# royer_1kw.net
KiCad netlist of a schematic drawn in EAGLE
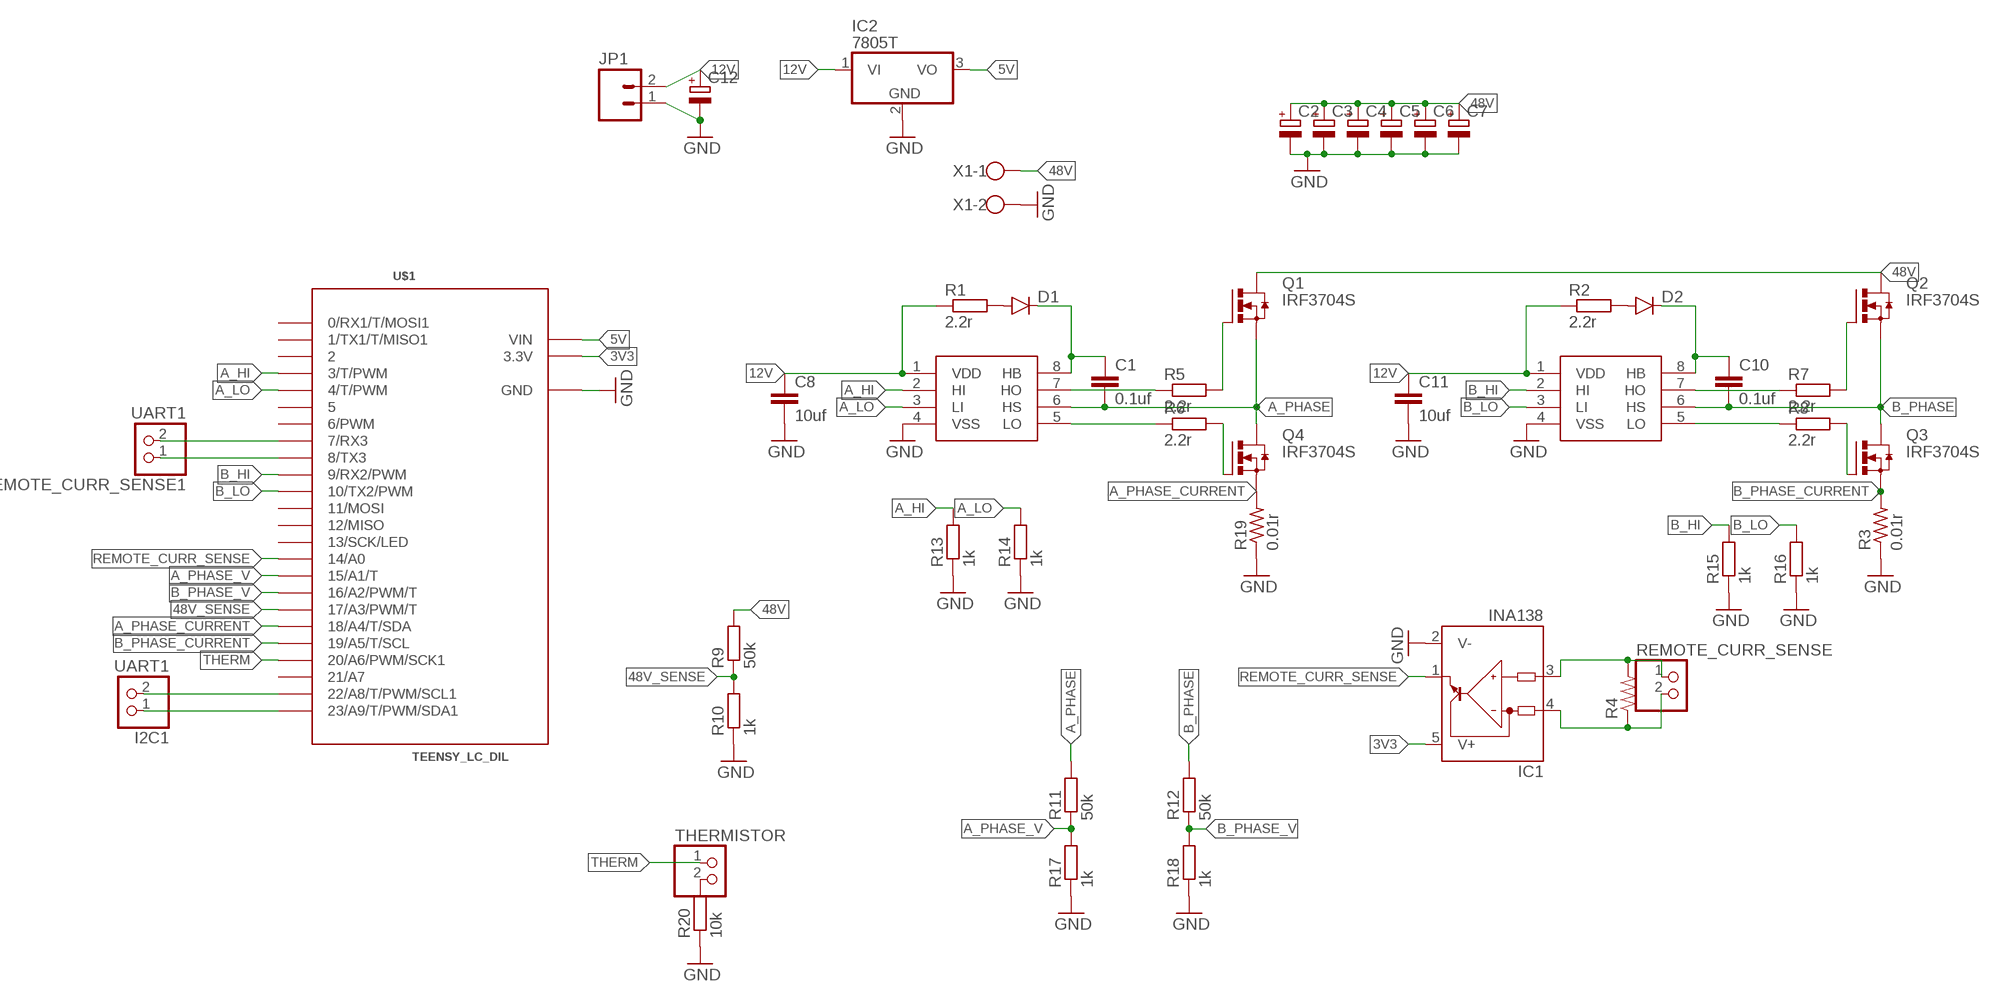
[diagram p0: schematic, sheet 1]

(export (version "E")
  (design (tool "Eeschema 10.0.6"))
  (components
    (comp (ref "C1")
      (value "0.1uf")
      (footprint "eagle-import:C0603")
      (libsource (lib "eagle-import") (part "C-EUC0603"))
    )
    (comp (ref "C2")
      (value "CPOL-EUE7.5-16")
      (footprint "eagle-import:E7,5-16")
      (libsource (lib "eagle-import") (part "CPOL-EUE7.5-16"))
    )
    (comp (ref "C3")
      (value "CPOL-EUE7.5-16")
      (footprint "eagle-import:E7,5-16")
      (libsource (lib "eagle-import") (part "CPOL-EUE7.5-16"))
    )
    (comp (ref "C4")
      (value "CPOL-EUE7.5-16")
      (footprint "eagle-import:E7,5-16")
      (libsource (lib "eagle-import") (part "CPOL-EUE7.5-16"))
    )
    (comp (ref "C5")
      (value "CPOL-EUE7.5-16")
      (footprint "eagle-import:E7,5-16")
      (libsource (lib "eagle-import") (part "CPOL-EUE7.5-16"))
    )
    (comp (ref "C6")
      (value "CPOL-EUE7.5-16")
      (footprint "eagle-import:E7,5-16")
      (libsource (lib "eagle-import") (part "CPOL-EUE7.5-16"))
    )
    (comp (ref "C7")
      (value "CPOL-EUE7.5-16")
      (footprint "eagle-import:E7,5-16")
      (libsource (lib "eagle-import") (part "CPOL-EUE7.5-16"))
    )
    (comp (ref "C8")
      (value "10uf")
      (footprint "eagle-import:C0805")
      (libsource (lib "eagle-import") (part "C-EUC0805"))
    )
    (comp (ref "C10")
      (value "0.1uf")
      (footprint "eagle-import:C0603")
      (libsource (lib "eagle-import") (part "C-EUC0603"))
    )
    (comp (ref "C11")
      (value "10uf")
      (footprint "eagle-import:C0805")
      (libsource (lib "eagle-import") (part "C-EUC0805"))
    )
    (comp (ref "C12")
      (value "CPOL-EUE2.5-7")
      (footprint "eagle-import:E2,5-7")
      (libsource (lib "eagle-import") (part "CPOL-EUE2.5-7"))
    )
    (comp (ref "D1")
      (value "DIODESMA")
      (footprint "eagle-import:SMA-DIODE")
      (libsource (lib "eagle-import") (part "DIODESMA"))
    )
    (comp (ref "D2")
      (value "DIODESMA")
      (footprint "eagle-import:SMA-DIODE")
      (libsource (lib "eagle-import") (part "DIODESMA"))
    )
    (comp (ref "I2C1")
      (value "UART1")
      (footprint "eagle-import:1X02")
      (libsource (lib "eagle-import") (part "PINHD-1X2"))
    )
    (comp (ref "IC1")
      (value "INA138")
      (footprint "eagle-import:SOT23-5")
      (fields (field (name "MF") "TEXAS INSTRUMENTS") (field (name "MPN") "INA138NA/250"))
      (libsource (lib "eagle-import") (part "INA138"))
    )
    (comp (ref "IC2")
      (value "7805T")
      (footprint "eagle-import:TO220H")
      (libsource (lib "eagle-import") (part "78T05"))
    )
    (comp (ref "JP1")
      (value "M023.5MM")
      (footprint "eagle-import:SCREWTERMINAL-3.5MM-2")
      (libsource (lib "eagle-import") (part "M023.5MM"))
    )
    (comp (ref "Q1")
      (value "IRF3704S")
      (footprint "eagle-import:D2PACK")
      (libsource (lib "eagle-import") (part "IRF3704S"))
    )
    (comp (ref "Q2")
      (value "IRF3704S")
      (footprint "eagle-import:D2PACK")
      (libsource (lib "eagle-import") (part "IRF3704S"))
    )
    (comp (ref "Q3")
      (value "IRF3704S")
      (footprint "eagle-import:D2PACK")
      (libsource (lib "eagle-import") (part "IRF3704S"))
    )
    (comp (ref "Q4")
      (value "IRF3704S")
      (footprint "eagle-import:D2PACK")
      (libsource (lib "eagle-import") (part "IRF3704S"))
    )
    (comp (ref "R1")
      (value "2.2r")
      (footprint "eagle-import:R1210")
      (libsource (lib "eagle-import") (part "R-EU_R1210"))
    )
    (comp (ref "R2")
      (value "2.2r")
      (footprint "eagle-import:R1210")
      (libsource (lib "eagle-import") (part "R-EU_R1210"))
    )
    (comp (ref "R3")
      (value "0.01r")
      (footprint "eagle-import:R3225")
      (libsource (lib "eagle-import") (part "R-US_R3225"))
    )
    (comp (ref "R4")
      (value "RESISTOR1206")
      (footprint "eagle-import:1206")
      (libsource (lib "eagle-import") (part "RESISTOR1206"))
    )
    (comp (ref "R5")
      (value "2.2r")
      (footprint "eagle-import:R1210")
      (libsource (lib "eagle-import") (part "R-EU_R1210"))
    )
    (comp (ref "R6")
      (value "2.2r")
      (footprint "eagle-import:R1210")
      (libsource (lib "eagle-import") (part "R-EU_R1210"))
    )
    (comp (ref "R7")
      (value "2.2r")
      (footprint "eagle-import:R1210")
      (libsource (lib "eagle-import") (part "R-EU_R1210"))
    )
    (comp (ref "R8")
      (value "2.2r")
      (footprint "eagle-import:R1210")
      (libsource (lib "eagle-import") (part "R-EU_R1210"))
    )
    (comp (ref "R9")
      (value "50k")
      (footprint "eagle-import:R0603")
      (libsource (lib "eagle-import") (part "R-EU_R0603"))
    )
    (comp (ref "R10")
      (value "1k")
      (footprint "eagle-import:R0603")
      (libsource (lib "eagle-import") (part "R-EU_R0603"))
    )
    (comp (ref "R11")
      (value "50k")
      (footprint "eagle-import:R0603")
      (libsource (lib "eagle-import") (part "R-EU_R0603"))
    )
    (comp (ref "R12")
      (value "50k")
      (footprint "eagle-import:R0603")
      (libsource (lib "eagle-import") (part "R-EU_R0603"))
    )
    (comp (ref "R13")
      (value "1k")
      (footprint "eagle-import:R0603")
      (libsource (lib "eagle-import") (part "R-EU_R0603"))
    )
    (comp (ref "R14")
      (value "1k")
      (footprint "eagle-import:R0603")
      (libsource (lib "eagle-import") (part "R-EU_R0603"))
    )
    (comp (ref "R15")
      (value "1k")
      (footprint "eagle-import:R0603")
      (libsource (lib "eagle-import") (part "R-EU_R0603"))
    )
    (comp (ref "R16")
      (value "1k")
      (footprint "eagle-import:R0603")
      (libsource (lib "eagle-import") (part "R-EU_R0603"))
    )
    (comp (ref "R17")
      (value "1k")
      (footprint "eagle-import:R0603")
      (libsource (lib "eagle-import") (part "R-EU_R0603"))
    )
    (comp (ref "R18")
      (value "1k")
      (footprint "eagle-import:R0603")
      (libsource (lib "eagle-import") (part "R-EU_R0603"))
    )
    (comp (ref "R19")
      (value "0.01r")
      (footprint "eagle-import:R3225")
      (libsource (lib "eagle-import") (part "R-US_R3225"))
    )
    (comp (ref "R20")
      (value "10k")
      (footprint "eagle-import:R0603")
      (libsource (lib "eagle-import") (part "R-EU_R0603"))
    )
    (comp (ref "REMOTE_CURR_SENSE")
      (value "PINHD-1X2")
      (footprint "eagle-import:1X02")
      (libsource (lib "eagle-import") (part "PINHD-1X2"))
    )
    (comp (ref "REMOTE_CURR_SENSE1")
      (value "UART1")
      (footprint "eagle-import:1X02")
      (libsource (lib "eagle-import") (part "PINHD-1X2"))
    )
    (comp (ref "THERMISTOR")
      (value "PINHD-1X2")
      (footprint "eagle-import:1X02")
      (libsource (lib "eagle-import") (part "PINHD-1X2"))
    )
    (comp (ref "U$1")
      (value "TEENSY_LC_DIL")
      (footprint "eagle-import:TEENSY_3.0-3.2&LC_DIL")
      (libsource (lib "eagle-import") (part "TEENSY_LC_DIL"))
    )
    (comp (ref "U$2")
      (value "LM5109")
      (footprint "eagle-import:SOIC8")
      (libsource (lib "eagle-import") (part "LM5109"))
    )
    (comp (ref "U$4")
      (value "LM5109")
      (footprint "eagle-import:SOIC8")
      (libsource (lib "eagle-import") (part "LM5109"))
    )
    (comp (ref "X1")
      (value "W237-102")
      (footprint "eagle-import:W237-102")
      (fields (field (name "MPN") "237-102"))
      (libsource (lib "eagle-import") (part "W237-102"))
    )
  )
  (nets
    (net (code "1") (name "3V3") (class "Default")
      (node (ref "IC1") (pin "5") (pinfunction "V+_5") (pintype "power_in"))
      (node (ref "U$1") (pin "3.3V") (pinfunction "3.3V_3.3V") (pintype "power_in"))
    )
    (net (code "2") (name "5V") (class "Default")
      (node (ref "IC2") (pin "3") (pinfunction "VO_3") (pintype "passive"))
      (node (ref "U$1") (pin "VIN") (pinfunction "VIN_VIN") (pintype "power_in"))
    )
    (net (code "3") (name "12V") (class "Default")
      (node (ref "C11") (pin "1") (pinfunction "1_1") (pintype "passive"))
      (node (ref "C12") (pin "+") (pinfunction "+_+") (pintype "passive"))
      (node (ref "C8") (pin "1") (pinfunction "1_1") (pintype "passive"))
      (node (ref "IC2") (pin "1") (pinfunction "VI_1") (pintype "input"))
      (node (ref "JP1") (pin "2") (pinfunction "2_2") (pintype "passive"))
      (node (ref "R1") (pin "1") (pinfunction "1_1") (pintype "passive"))
      (node (ref "R2") (pin "1") (pinfunction "1_1") (pintype "passive"))
      (node (ref "U$2") (pin "1") (pinfunction "VDD_1") (pintype "bidirectional"))
      (node (ref "U$4") (pin "1") (pinfunction "VDD_1") (pintype "bidirectional"))
    )
    (net (code "4") (name "48V") (class "Default")
      (node (ref "C2") (pin "+") (pinfunction "+_+") (pintype "passive"))
      (node (ref "C3") (pin "+") (pinfunction "+_+") (pintype "passive"))
      (node (ref "C4") (pin "+") (pinfunction "+_+") (pintype "passive"))
      (node (ref "C5") (pin "+") (pinfunction "+_+") (pintype "passive"))
      (node (ref "C6") (pin "+") (pinfunction "+_+") (pintype "passive"))
      (node (ref "C7") (pin "+") (pinfunction "+_+") (pintype "passive"))
      (node (ref "Q1") (pin "2") (pinfunction "D_2") (pintype "passive"))
      (node (ref "Q2") (pin "2") (pinfunction "D_2") (pintype "passive"))
      (node (ref "R9") (pin "2") (pinfunction "2_2") (pintype "passive"))
      (node (ref "X1") (pin "1") (pinfunction "KL_1") (pintype "passive"))
    )
    (net (code "5") (name "48V_SENSE") (class "Default")
      (node (ref "R10") (pin "2") (pinfunction "2_2") (pintype "passive"))
      (node (ref "R9") (pin "1") (pinfunction "1_1") (pintype "passive"))
      (node (ref "U$1") (pin "17/A3") (pinfunction "17/A3/PWM/T_17/A3") (pintype "bidirectional"))
    )
    (net (code "6") (name "A_HI") (class "Default")
      (node (ref "R13") (pin "2") (pinfunction "2_2") (pintype "passive"))
      (node (ref "U$1") (pin "3") (pinfunction "3/T/PWM_3") (pintype "bidirectional"))
      (node (ref "U$2") (pin "2") (pinfunction "HI_2") (pintype "bidirectional"))
    )
    (net (code "7") (name "A_LO") (class "Default")
      (node (ref "R14") (pin "2") (pinfunction "2_2") (pintype "passive"))
      (node (ref "U$1") (pin "4") (pinfunction "4/T/PWM_4") (pintype "bidirectional"))
      (node (ref "U$2") (pin "3") (pinfunction "LI_3") (pintype "bidirectional"))
    )
    (net (code "8") (name "A_PHASE") (class "Default")
      (node (ref "C1") (pin "2") (pinfunction "2_2") (pintype "passive"))
      (node (ref "Q1") (pin "3") (pinfunction "S_3") (pintype "passive"))
      (node (ref "Q4") (pin "2") (pinfunction "D_2") (pintype "passive"))
      (node (ref "R11") (pin "2") (pinfunction "2_2") (pintype "passive"))
      (node (ref "U$2") (pin "6") (pinfunction "HS_6") (pintype "bidirectional"))
    )
    (net (code "9") (name "A_PHASE_CURRENT") (class "Default")
      (node (ref "Q4") (pin "3") (pinfunction "S_3") (pintype "passive"))
      (node (ref "R19") (pin "2") (pinfunction "2_2") (pintype "passive"))
      (node (ref "U$1") (pin "18/A4") (pinfunction "18/A4/T/SDA_18/A4") (pintype "bidirectional"))
    )
    (net (code "10") (name "A_PHASE_V") (class "Default")
      (node (ref "R11") (pin "1") (pinfunction "1_1") (pintype "passive"))
      (node (ref "R17") (pin "2") (pinfunction "2_2") (pintype "passive"))
      (node (ref "U$1") (pin "15/A1") (pinfunction "15/A1/T_15/A1") (pintype "bidirectional"))
    )
    (net (code "11") (name "B_HI") (class "Default")
      (node (ref "R15") (pin "2") (pinfunction "2_2") (pintype "passive"))
      (node (ref "U$1") (pin "9") (pinfunction "9/RX2/PWM_9") (pintype "bidirectional"))
      (node (ref "U$4") (pin "2") (pinfunction "HI_2") (pintype "bidirectional"))
    )
    (net (code "12") (name "B_LO") (class "Default")
      (node (ref "R16") (pin "2") (pinfunction "2_2") (pintype "passive"))
      (node (ref "U$1") (pin "10") (pinfunction "10/TX2/PWM_10") (pintype "bidirectional"))
      (node (ref "U$4") (pin "3") (pinfunction "LI_3") (pintype "bidirectional"))
    )
    (net (code "13") (name "B_PHASE") (class "Default")
      (node (ref "C10") (pin "2") (pinfunction "2_2") (pintype "passive"))
      (node (ref "Q2") (pin "3") (pinfunction "S_3") (pintype "passive"))
      (node (ref "Q3") (pin "2") (pinfunction "D_2") (pintype "passive"))
      (node (ref "R12") (pin "2") (pinfunction "2_2") (pintype "passive"))
      (node (ref "U$4") (pin "6") (pinfunction "HS_6") (pintype "bidirectional"))
    )
    (net (code "14") (name "B_PHASE_CURRENT") (class "Default")
      (node (ref "Q3") (pin "3") (pinfunction "S_3") (pintype "passive"))
      (node (ref "R3") (pin "2") (pinfunction "2_2") (pintype "passive"))
      (node (ref "U$1") (pin "19/A5") (pinfunction "19/A5/T/SCL_19/A5") (pintype "bidirectional"))
    )
    (net (code "15") (name "B_PHASE_V") (class "Default")
      (node (ref "R12") (pin "1") (pinfunction "1_1") (pintype "passive"))
      (node (ref "R18") (pin "2") (pinfunction "2_2") (pintype "passive"))
      (node (ref "U$1") (pin "16/A2") (pinfunction "16/A2/PWM/T_16/A2") (pintype "bidirectional"))
    )
    (net (code "16") (name "GND") (class "Default")
      (node (ref "C11") (pin "2") (pinfunction "2_2") (pintype "passive"))
      (node (ref "C12") (pin "-") (pinfunction "-_-") (pintype "passive"))
      (node (ref "C2") (pin "-") (pinfunction "-_-") (pintype "passive"))
      (node (ref "C3") (pin "-") (pinfunction "-_-") (pintype "passive"))
      (node (ref "C4") (pin "-") (pinfunction "-_-") (pintype "passive"))
      (node (ref "C5") (pin "-") (pinfunction "-_-") (pintype "passive"))
      (node (ref "C6") (pin "-") (pinfunction "-_-") (pintype "passive"))
      (node (ref "C7") (pin "-") (pinfunction "-_-") (pintype "passive"))
      (node (ref "C8") (pin "2") (pinfunction "2_2") (pintype "passive"))
      (node (ref "IC1") (pin "2") (pinfunction "V-_2") (pintype "power_in"))
      (node (ref "IC2") (pin "2") (pinfunction "GND_2") (pintype "passive"))
      (node (ref "JP1") (pin "1") (pinfunction "1_1") (pintype "passive"))
      (node (ref "R10") (pin "1") (pinfunction "1_1") (pintype "passive"))
      (node (ref "R13") (pin "1") (pinfunction "1_1") (pintype "passive"))
      (node (ref "R14") (pin "1") (pinfunction "1_1") (pintype "passive"))
      (node (ref "R15") (pin "1") (pinfunction "1_1") (pintype "passive"))
      (node (ref "R16") (pin "1") (pinfunction "1_1") (pintype "passive"))
      (node (ref "R17") (pin "1") (pinfunction "1_1") (pintype "passive"))
      (node (ref "R18") (pin "1") (pinfunction "1_1") (pintype "passive"))
      (node (ref "R19") (pin "1") (pinfunction "1_1") (pintype "passive"))
      (node (ref "R20") (pin "1") (pinfunction "1_1") (pintype "passive"))
      (node (ref "R3") (pin "1") (pinfunction "1_1") (pintype "passive"))
      (node (ref "U$1") (pin "AGND") (pinfunction "GND_AGND") (pintype "power_in"))
      (node (ref "U$1") (pin "GND") (pinfunction "GND_GND") (pintype "power_in"))
      (node (ref "U$2") (pin "4") (pinfunction "VSS_4") (pintype "bidirectional"))
      (node (ref "U$4") (pin "4") (pinfunction "VSS_4") (pintype "bidirectional"))
      (node (ref "X1") (pin "2") (pinfunction "KL_2") (pintype "passive"))
    )
    (net (code "17") (name "Net-(D1-PadA)") (class "Default")
      (node (ref "D1") (pin "A") (pinfunction "A_A") (pintype "passive"))
      (node (ref "R1") (pin "2") (pinfunction "2_2") (pintype "passive"))
    )
    (net (code "18") (name "Net-(D2-PadA)") (class "Default")
      (node (ref "D2") (pin "A") (pinfunction "A_A") (pintype "passive"))
      (node (ref "R2") (pin "2") (pinfunction "2_2") (pintype "passive"))
    )
    (net (code "19") (name "Net-(IC1-IN+)") (class "Default")
      (node (ref "IC1") (pin "3") (pinfunction "IN+_3") (pintype "input"))
      (node (ref "R4") (pin "2") (pinfunction "2_2") (pintype "passive"))
      (node (ref "REMOTE_CURR_SENSE") (pin "1") (pinfunction "1_1") (pintype "passive"))
    )
    (net (code "20") (name "Net-(IC1-IN-)") (class "Default")
      (node (ref "IC1") (pin "4") (pinfunction "IN-_4") (pintype "input"))
      (node (ref "R4") (pin "1") (pinfunction "1_1") (pintype "passive"))
      (node (ref "REMOTE_CURR_SENSE") (pin "2") (pinfunction "2_2") (pintype "passive"))
    )
    (net (code "21") (name "Net-(Q1-G)") (class "Default")
      (node (ref "Q1") (pin "1") (pinfunction "G_1") (pintype "passive"))
      (node (ref "R5") (pin "2") (pinfunction "2_2") (pintype "passive"))
    )
    (net (code "22") (name "Net-(Q2-G)") (class "Default")
      (node (ref "Q2") (pin "1") (pinfunction "G_1") (pintype "passive"))
      (node (ref "R7") (pin "2") (pinfunction "2_2") (pintype "passive"))
    )
    (net (code "23") (name "Net-(Q3-G)") (class "Default")
      (node (ref "Q3") (pin "1") (pinfunction "G_1") (pintype "passive"))
      (node (ref "R8") (pin "2") (pinfunction "2_2") (pintype "passive"))
    )
    (net (code "24") (name "Net-(Q4-G)") (class "Default")
      (node (ref "Q4") (pin "1") (pinfunction "G_1") (pintype "passive"))
      (node (ref "R6") (pin "2") (pinfunction "2_2") (pintype "passive"))
    )
    (net (code "25") (name "Net-(R20-Pad2)") (class "Default")
      (node (ref "R20") (pin "2") (pinfunction "2_2") (pintype "passive"))
      (node (ref "THERMISTOR") (pin "2") (pinfunction "2_2") (pintype "passive"))
    )
    (net (code "26") (name "Net-(U$1-7{slash}RX3)") (class "Default")
      (node (ref "REMOTE_CURR_SENSE1") (pin "2") (pinfunction "2_2") (pintype "passive"))
      (node (ref "U$1") (pin "7") (pinfunction "7/RX3_7") (pintype "bidirectional"))
    )
    (net (code "27") (name "Net-(U$1-8{slash}TX3)") (class "Default")
      (node (ref "REMOTE_CURR_SENSE1") (pin "1") (pinfunction "1_1") (pintype "passive"))
      (node (ref "U$1") (pin "8") (pinfunction "8/TX3_8") (pintype "bidirectional"))
    )
    (net (code "28") (name "Net-(U$1-22{slash}A8{slash}T{slash}PWM{slash}SCL1)") (class "Default")
      (node (ref "I2C1") (pin "2") (pinfunction "2_2") (pintype "passive"))
      (node (ref "U$1") (pin "22/A8") (pinfunction "22/A8/T/PWM/SCL1_22/A8") (pintype "bidirectional"))
    )
    (net (code "29") (name "Net-(U$1-23{slash}A9{slash}T{slash}PWM{slash}SDA1)") (class "Default")
      (node (ref "I2C1") (pin "1") (pinfunction "1_1") (pintype "passive"))
      (node (ref "U$1") (pin "23/A9") (pinfunction "23/A9/T/PWM/SDA1_23/A9") (pintype "bidirectional"))
    )
    (net (code "30") (name "Net-(U$2-HB)") (class "Default")
      (node (ref "C1") (pin "1") (pinfunction "1_1") (pintype "passive"))
      (node (ref "D1") (pin "C") (pinfunction "C_C") (pintype "passive"))
      (node (ref "U$2") (pin "8") (pinfunction "HB_8") (pintype "bidirectional"))
    )
    (net (code "31") (name "Net-(U$2-HO)") (class "Default")
      (node (ref "R5") (pin "1") (pinfunction "1_1") (pintype "passive"))
      (node (ref "U$2") (pin "7") (pinfunction "HO_7") (pintype "bidirectional"))
    )
    (net (code "32") (name "Net-(U$2-LO)") (class "Default")
      (node (ref "R6") (pin "1") (pinfunction "1_1") (pintype "passive"))
      (node (ref "U$2") (pin "5") (pinfunction "LO_5") (pintype "bidirectional"))
    )
    (net (code "33") (name "Net-(U$4-HB)") (class "Default")
      (node (ref "C10") (pin "1") (pinfunction "1_1") (pintype "passive"))
      (node (ref "D2") (pin "C") (pinfunction "C_C") (pintype "passive"))
      (node (ref "U$4") (pin "8") (pinfunction "HB_8") (pintype "bidirectional"))
    )
    (net (code "34") (name "Net-(U$4-HO)") (class "Default")
      (node (ref "R7") (pin "1") (pinfunction "1_1") (pintype "passive"))
      (node (ref "U$4") (pin "7") (pinfunction "HO_7") (pintype "bidirectional"))
    )
    (net (code "35") (name "Net-(U$4-LO)") (class "Default")
      (node (ref "R8") (pin "1") (pinfunction "1_1") (pintype "passive"))
      (node (ref "U$4") (pin "5") (pinfunction "LO_5") (pintype "bidirectional"))
    )
    (net (code "36") (name "REMOTE_CURR_SENSE") (class "Default")
      (node (ref "IC1") (pin "1") (pinfunction "OUT_1") (pintype "output"))
      (node (ref "U$1") (pin "14/A0") (pinfunction "14/A0_14/A0") (pintype "bidirectional"))
    )
    (net (code "37") (name "THERM") (class "Default")
      (node (ref "THERMISTOR") (pin "1") (pinfunction "1_1") (pintype "passive"))
      (node (ref "U$1") (pin "20/A6") (pinfunction "20/A6/PWM/SCK1_20/A6") (pintype "bidirectional"))
    )
    (net (code "38") (name "unconnected-(U$1-0{slash}RX1{slash}T{slash}MOSI1-Pad0)") (class "Default")
      (node (ref "U$1") (pin "0") (pinfunction "0/RX1/T/MOSI1_0") (pintype "bidirectional"))
    )
    (net (code "39") (name "unconnected-(U$1-1{slash}TX1{slash}T{slash}MISO1-Pad1)") (class "Default")
      (node (ref "U$1") (pin "1") (pinfunction "1/TX1/T/MISO1_1") (pintype "bidirectional"))
    )
    (net (code "40") (name "unconnected-(U$1-6{slash}PWM-Pad6)") (class "Default")
      (node (ref "U$1") (pin "6") (pinfunction "6/PWM_6") (pintype "bidirectional"))
    )
    (net (code "41") (name "unconnected-(U$1-11{slash}MOSI-Pad11)") (class "Default")
      (node (ref "U$1") (pin "11") (pinfunction "11/MOSI_11") (pintype "bidirectional"))
    )
    (net (code "42") (name "unconnected-(U$1-12{slash}MISO-Pad12)") (class "Default")
      (node (ref "U$1") (pin "12") (pinfunction "12/MISO_12") (pintype "bidirectional"))
    )
    (net (code "43") (name "unconnected-(U$1-13{slash}SCK{slash}LED-Pad13)") (class "Default")
      (node (ref "U$1") (pin "13") (pinfunction "13/SCK/LED_13") (pintype "bidirectional"))
    )
    (net (code "44") (name "unconnected-(U$1-Pad2)") (class "Default")
      (node (ref "U$1") (pin "2") (pinfunction "2_2") (pintype "bidirectional"))
    )
    (net (code "45") (name "unconnected-(U$1-Pad5)") (class "Default")
      (node (ref "U$1") (pin "5") (pinfunction "5_5") (pintype "bidirectional"))
    )
    (net (code "46") (name "unconnected-(U$1-Pad21{slash}A7)") (class "Default")
      (node (ref "U$1") (pin "21/A7") (pinfunction "21/A7_21/A7") (pintype "bidirectional"))
    )
  )
)
